# RaspNRF24.net
KiCad netlist of a schematic drawn in EAGLE
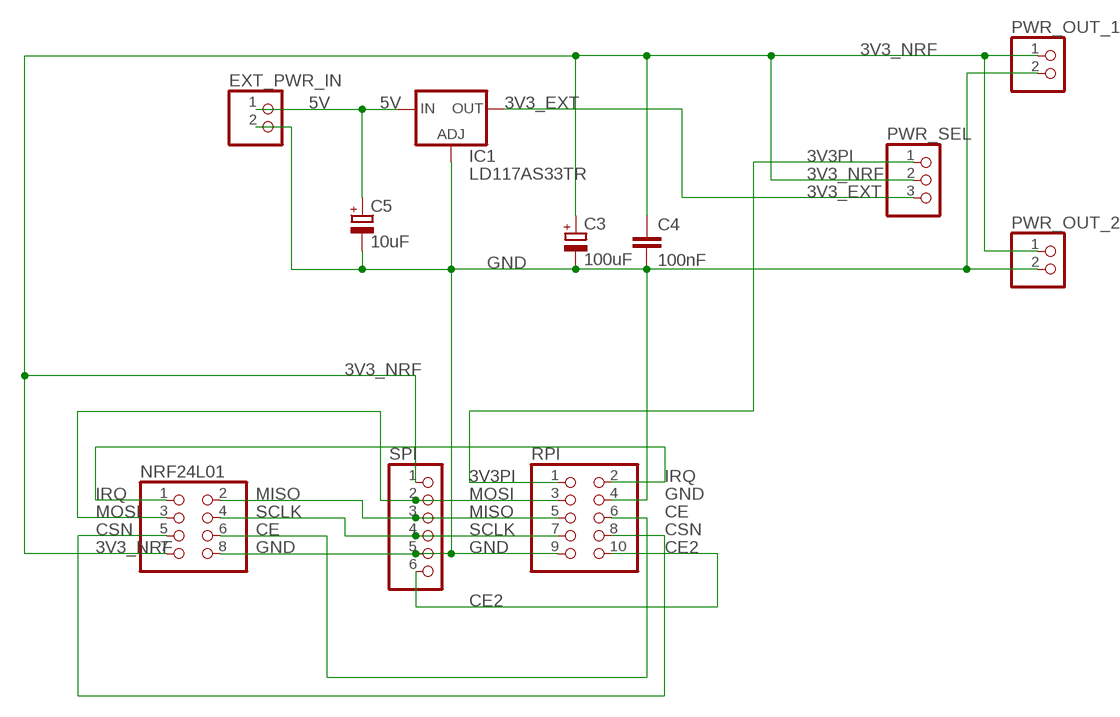
[diagram p0: schematic, sheet 1]

(export (version "E")
  (design (tool "Eeschema 10.0.6"))
  (components
    (comp (ref "C3")
      (value "100uF")
      (footprint "eagle-import:E2,5-5")
      (libsource (lib "eagle-import") (part "CPOL-EUE2.5-5"))
    )
    (comp (ref "C4")
      (value "100nF")
      (footprint "eagle-import:C025-024X044")
      (libsource (lib "eagle-import") (part "C-EU025-024X044"))
    )
    (comp (ref "C5")
      (value "10uF")
      (footprint "eagle-import:E2-4")
      (libsource (lib "eagle-import") (part "CPOL-EUE2-4"))
    )
    (comp (ref "EXT_PWR_IN")
      (value "PINHD-1X2")
      (footprint "eagle-import:1X02")
      (libsource (lib "eagle-import") (part "PINHD-1X2"))
    )
    (comp (ref "IC1")
      (value "LD117AS33TR")
      (footprint "eagle-import:SOT223")
      (libsource (lib "eagle-import") (part "LD117A?S33TR"))
    )
    (comp (ref "NRF24L01")
      (value "PINHD-2X4")
      (footprint "eagle-import:2X04")
      (libsource (lib "eagle-import") (part "PINHD-2X4"))
    )
    (comp (ref "PWR_OUT_1")
      (value "PINHD-1X2")
      (footprint "eagle-import:1X02")
      (libsource (lib "eagle-import") (part "PINHD-1X2"))
    )
    (comp (ref "PWR_OUT_2")
      (value "PINHD-1X2")
      (footprint "eagle-import:1X02")
      (libsource (lib "eagle-import") (part "pinheadHB_PINHD-1X2"))
    )
    (comp (ref "PWR_SEL")
      (value "PINHD-1X3")
      (footprint "eagle-import:1X03")
      (libsource (lib "eagle-import") (part "PINHD-1X3"))
    )
    (comp (ref "RPI")
      (value "PINHD-2X5")
      (footprint "eagle-import:2X05")
      (libsource (lib "eagle-import") (part "PINHD-2X5"))
    )
    (comp (ref "SPI")
      (value "PINHD-1X6")
      (footprint "eagle-import:1X06")
      (libsource (lib "eagle-import") (part "PINHD-1X6"))
    )
  )
  (nets
    (net (code "1") (name "/3V3PI") (class "Default")
      (node (ref "PWR_SEL") (pin "1") (pinfunction "1_1") (pintype "passive"))
      (node (ref "RPI") (pin "1") (pinfunction "1_1") (pintype "passive"))
    )
    (net (code "2") (name "/3V3_EXT") (class "Default")
      (node (ref "IC1") (pin "4") (pinfunction "OUT_4") (pintype "passive"))
      (node (ref "PWR_SEL") (pin "3") (pinfunction "3_3") (pintype "passive"))
    )
    (net (code "3") (name "/3V3_NRF") (class "Default")
      (node (ref "C3") (pin "+") (pinfunction "+_+") (pintype "passive"))
      (node (ref "C4") (pin "1") (pinfunction "1_1") (pintype "passive"))
      (node (ref "NRF24L01") (pin "7") (pinfunction "7_7") (pintype "passive"))
      (node (ref "PWR_OUT_1") (pin "1") (pinfunction "1_1") (pintype "passive"))
      (node (ref "PWR_OUT_2") (pin "1") (pinfunction "1_1") (pintype "passive"))
      (node (ref "PWR_SEL") (pin "2") (pinfunction "2_2") (pintype "passive"))
      (node (ref "SPI") (pin "1") (pinfunction "1_1") (pintype "passive"))
    )
    (net (code "4") (name "/5V") (class "Default")
      (node (ref "C5") (pin "+") (pinfunction "+_+") (pintype "passive"))
      (node (ref "EXT_PWR_IN") (pin "1") (pinfunction "1_1") (pintype "passive"))
      (node (ref "IC1") (pin "3") (pinfunction "IN_3") (pintype "input"))
    )
    (net (code "5") (name "/CE") (class "Default")
      (node (ref "NRF24L01") (pin "6") (pinfunction "6_6") (pintype "passive"))
      (node (ref "RPI") (pin "6") (pinfunction "6_6") (pintype "passive"))
    )
    (net (code "6") (name "/CE2") (class "Default")
      (node (ref "RPI") (pin "10") (pinfunction "10_10") (pintype "passive"))
      (node (ref "SPI") (pin "6") (pinfunction "6_6") (pintype "passive"))
    )
    (net (code "7") (name "/CSN") (class "Default")
      (node (ref "NRF24L01") (pin "5") (pinfunction "5_5") (pintype "passive"))
      (node (ref "RPI") (pin "8") (pinfunction "8_8") (pintype "passive"))
    )
    (net (code "8") (name "/GND") (class "Default")
      (node (ref "C3") (pin "-") (pinfunction "-_-") (pintype "passive"))
      (node (ref "C4") (pin "2") (pinfunction "2_2") (pintype "passive"))
      (node (ref "C5") (pin "-") (pinfunction "-_-") (pintype "passive"))
      (node (ref "EXT_PWR_IN") (pin "2") (pinfunction "2_2") (pintype "passive"))
      (node (ref "IC1") (pin "1") (pinfunction "ADJ_1") (pintype "input"))
      (node (ref "NRF24L01") (pin "8") (pinfunction "8_8") (pintype "passive"))
      (node (ref "PWR_OUT_1") (pin "2") (pinfunction "2_2") (pintype "passive"))
      (node (ref "PWR_OUT_2") (pin "2") (pinfunction "2_2") (pintype "passive"))
      (node (ref "RPI") (pin "4") (pinfunction "4_4") (pintype "passive"))
      (node (ref "RPI") (pin "9") (pinfunction "9_9") (pintype "passive"))
      (node (ref "SPI") (pin "5") (pinfunction "5_5") (pintype "passive"))
    )
    (net (code "9") (name "/IRQ") (class "Default")
      (node (ref "NRF24L01") (pin "1") (pinfunction "1_1") (pintype "passive"))
      (node (ref "RPI") (pin "2") (pinfunction "2_2") (pintype "passive"))
    )
    (net (code "10") (name "/MISO") (class "Default")
      (node (ref "NRF24L01") (pin "2") (pinfunction "2_2") (pintype "passive"))
      (node (ref "RPI") (pin "5") (pinfunction "5_5") (pintype "passive"))
      (node (ref "SPI") (pin "3") (pinfunction "3_3") (pintype "passive"))
    )
    (net (code "11") (name "/MOSI") (class "Default")
      (node (ref "NRF24L01") (pin "3") (pinfunction "3_3") (pintype "passive"))
      (node (ref "RPI") (pin "3") (pinfunction "3_3") (pintype "passive"))
      (node (ref "SPI") (pin "2") (pinfunction "2_2") (pintype "passive"))
    )
    (net (code "12") (name "/SCLK") (class "Default")
      (node (ref "NRF24L01") (pin "4") (pinfunction "4_4") (pintype "passive"))
      (node (ref "RPI") (pin "7") (pinfunction "7_7") (pintype "passive"))
      (node (ref "SPI") (pin "4") (pinfunction "4_4") (pintype "passive"))
    )
  )
)
